# OpenAGBoardPart2.net
KiCad netlist of a schematic drawn in EAGLE
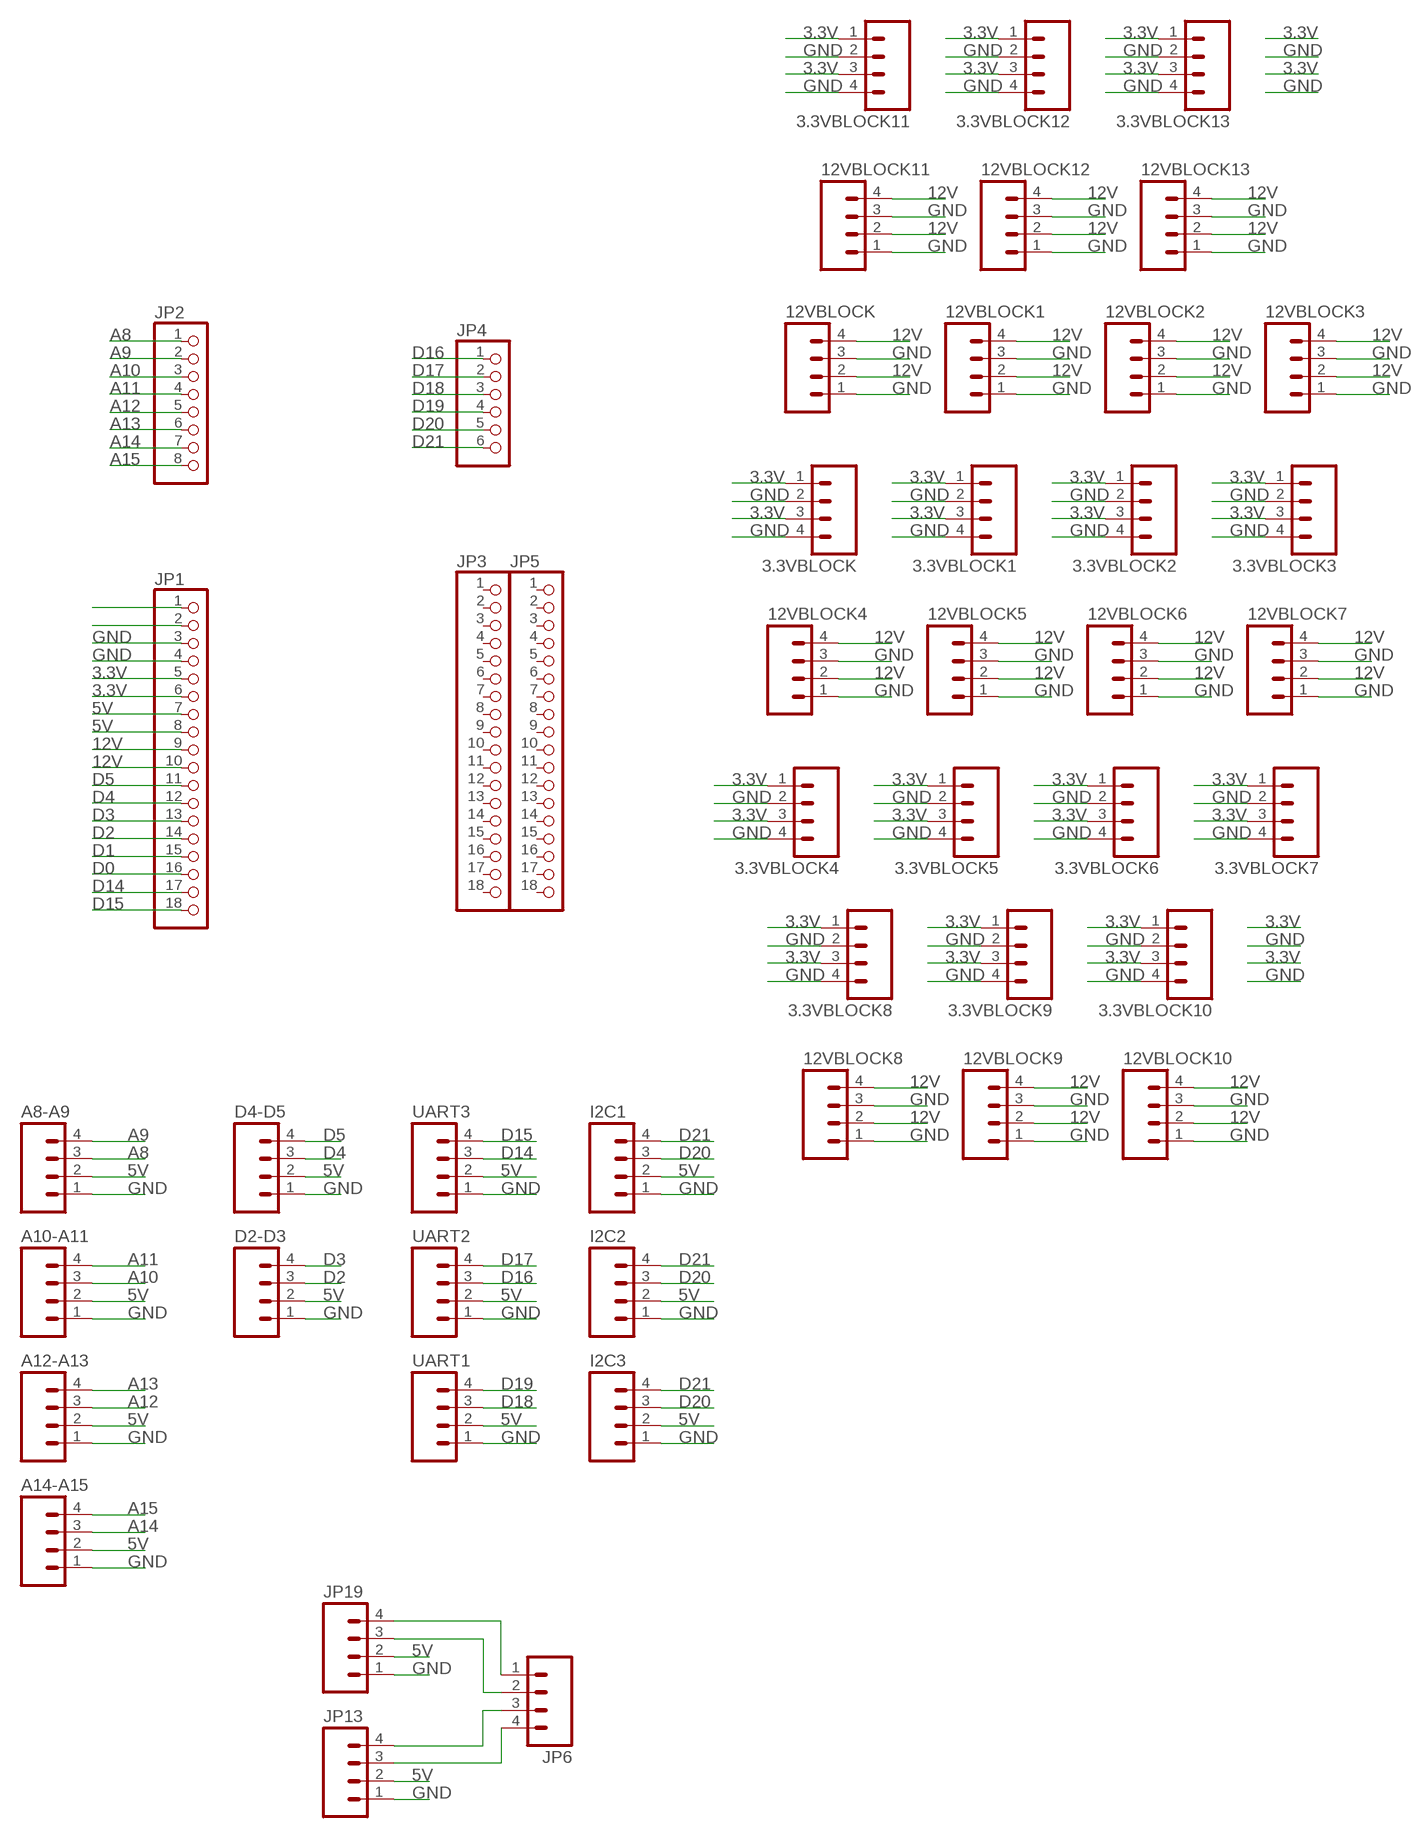
[diagram p0: schematic, sheet 1]

(export (version "E")
  (design (tool "Eeschema 10.0.6"))
  (components
    (comp (ref "3.3VBLOCK")
      (value "M04NO_SILK_ALL_ROUND")
      (footprint "eagle-import:1X04_NO_SILK_ALL_ROUND")
      (libsource (lib "eagle-import") (part "M04NO_SILK_ALL_ROUND"))
    )
    (comp (ref "3.3VBLOCK1")
      (value "M04NO_SILK_ALL_ROUND")
      (footprint "eagle-import:1X04_NO_SILK_ALL_ROUND")
      (libsource (lib "eagle-import") (part "M04NO_SILK_ALL_ROUND"))
    )
    (comp (ref "3.3VBLOCK2")
      (value "M04NO_SILK_ALL_ROUND")
      (footprint "eagle-import:1X04_NO_SILK_ALL_ROUND")
      (libsource (lib "eagle-import") (part "M04NO_SILK_ALL_ROUND"))
    )
    (comp (ref "3.3VBLOCK3")
      (value "M04NO_SILK_ALL_ROUND")
      (footprint "eagle-import:1X04_NO_SILK_ALL_ROUND")
      (libsource (lib "eagle-import") (part "M04NO_SILK_ALL_ROUND"))
    )
    (comp (ref "3.3VBLOCK4")
      (value "M04NO_SILK_ALL_ROUND")
      (footprint "eagle-import:1X04_NO_SILK_ALL_ROUND")
      (libsource (lib "eagle-import") (part "M04NO_SILK_ALL_ROUND"))
    )
    (comp (ref "3.3VBLOCK5")
      (value "M04NO_SILK_ALL_ROUND")
      (footprint "eagle-import:1X04_NO_SILK_ALL_ROUND")
      (libsource (lib "eagle-import") (part "M04NO_SILK_ALL_ROUND"))
    )
    (comp (ref "3.3VBLOCK6")
      (value "M04NO_SILK_ALL_ROUND")
      (footprint "eagle-import:1X04_NO_SILK_ALL_ROUND")
      (libsource (lib "eagle-import") (part "M04NO_SILK_ALL_ROUND"))
    )
    (comp (ref "3.3VBLOCK7")
      (value "M04NO_SILK_ALL_ROUND")
      (footprint "eagle-import:1X04_NO_SILK_ALL_ROUND")
      (libsource (lib "eagle-import") (part "M04NO_SILK_ALL_ROUND"))
    )
    (comp (ref "3.3VBLOCK8")
      (value "M04NO_SILK_ALL_ROUND")
      (footprint "eagle-import:1X04_NO_SILK_ALL_ROUND")
      (libsource (lib "eagle-import") (part "M04NO_SILK_ALL_ROUND"))
    )
    (comp (ref "3.3VBLOCK9")
      (value "M04NO_SILK_ALL_ROUND")
      (footprint "eagle-import:1X04_NO_SILK_ALL_ROUND")
      (libsource (lib "eagle-import") (part "M04NO_SILK_ALL_ROUND"))
    )
    (comp (ref "3.3VBLOCK10")
      (value "M04NO_SILK_ALL_ROUND")
      (footprint "eagle-import:1X04_NO_SILK_ALL_ROUND")
      (libsource (lib "eagle-import") (part "M04NO_SILK_ALL_ROUND"))
    )
    (comp (ref "3.3VBLOCK11")
      (value "M04NO_SILK_ALL_ROUND")
      (footprint "eagle-import:1X04_NO_SILK_ALL_ROUND")
      (libsource (lib "eagle-import") (part "M04NO_SILK_ALL_ROUND"))
    )
    (comp (ref "3.3VBLOCK12")
      (value "M04NO_SILK_ALL_ROUND")
      (footprint "eagle-import:1X04_NO_SILK_ALL_ROUND")
      (libsource (lib "eagle-import") (part "M04NO_SILK_ALL_ROUND"))
    )
    (comp (ref "3.3VBLOCK13")
      (value "M04NO_SILK_ALL_ROUND")
      (footprint "eagle-import:1X04_NO_SILK_ALL_ROUND")
      (libsource (lib "eagle-import") (part "M04NO_SILK_ALL_ROUND"))
    )
    (comp (ref "12VBLOCK")
      (value "M04NO_SILK_ALL_ROUND")
      (footprint "eagle-import:1X04_NO_SILK_ALL_ROUND")
      (libsource (lib "eagle-import") (part "M04NO_SILK_ALL_ROUND"))
    )
    (comp (ref "12VBLOCK1")
      (value "M04NO_SILK_ALL_ROUND")
      (footprint "eagle-import:1X04_NO_SILK_ALL_ROUND")
      (libsource (lib "eagle-import") (part "M04NO_SILK_ALL_ROUND"))
    )
    (comp (ref "12VBLOCK2")
      (value "M04NO_SILK_ALL_ROUND")
      (footprint "eagle-import:1X04_NO_SILK_ALL_ROUND")
      (libsource (lib "eagle-import") (part "M04NO_SILK_ALL_ROUND"))
    )
    (comp (ref "12VBLOCK3")
      (value "M04NO_SILK_ALL_ROUND")
      (footprint "eagle-import:1X04_NO_SILK_ALL_ROUND")
      (libsource (lib "eagle-import") (part "M04NO_SILK_ALL_ROUND"))
    )
    (comp (ref "12VBLOCK4")
      (value "M04NO_SILK_ALL_ROUND")
      (footprint "eagle-import:1X04_NO_SILK_ALL_ROUND")
      (libsource (lib "eagle-import") (part "M04NO_SILK_ALL_ROUND"))
    )
    (comp (ref "12VBLOCK5")
      (value "M04NO_SILK_ALL_ROUND")
      (footprint "eagle-import:1X04_NO_SILK_ALL_ROUND")
      (libsource (lib "eagle-import") (part "M04NO_SILK_ALL_ROUND"))
    )
    (comp (ref "12VBLOCK6")
      (value "M04NO_SILK_ALL_ROUND")
      (footprint "eagle-import:1X04_NO_SILK_ALL_ROUND")
      (libsource (lib "eagle-import") (part "M04NO_SILK_ALL_ROUND"))
    )
    (comp (ref "12VBLOCK7")
      (value "M04NO_SILK_ALL_ROUND")
      (footprint "eagle-import:1X04_NO_SILK_ALL_ROUND")
      (libsource (lib "eagle-import") (part "M04NO_SILK_ALL_ROUND"))
    )
    (comp (ref "12VBLOCK8")
      (value "M04NO_SILK_ALL_ROUND")
      (footprint "eagle-import:1X04_NO_SILK_ALL_ROUND")
      (libsource (lib "eagle-import") (part "M04NO_SILK_ALL_ROUND"))
    )
    (comp (ref "12VBLOCK9")
      (value "M04NO_SILK_ALL_ROUND")
      (footprint "eagle-import:1X04_NO_SILK_ALL_ROUND")
      (libsource (lib "eagle-import") (part "M04NO_SILK_ALL_ROUND"))
    )
    (comp (ref "12VBLOCK10")
      (value "M04NO_SILK_ALL_ROUND")
      (footprint "eagle-import:1X04_NO_SILK_ALL_ROUND")
      (libsource (lib "eagle-import") (part "M04NO_SILK_ALL_ROUND"))
    )
    (comp (ref "12VBLOCK11")
      (value "M04NO_SILK_ALL_ROUND")
      (footprint "eagle-import:1X04_NO_SILK_ALL_ROUND")
      (libsource (lib "eagle-import") (part "M04NO_SILK_ALL_ROUND"))
    )
    (comp (ref "12VBLOCK12")
      (value "M04NO_SILK_ALL_ROUND")
      (footprint "eagle-import:1X04_NO_SILK_ALL_ROUND")
      (libsource (lib "eagle-import") (part "M04NO_SILK_ALL_ROUND"))
    )
    (comp (ref "12VBLOCK13")
      (value "M04NO_SILK_ALL_ROUND")
      (footprint "eagle-import:1X04_NO_SILK_ALL_ROUND")
      (libsource (lib "eagle-import") (part "M04NO_SILK_ALL_ROUND"))
    )
    (comp (ref "A8-A9")
      (value "M04NO_SILK_ALL_ROUND")
      (footprint "eagle-import:1X04_NO_SILK_ALL_ROUND")
      (libsource (lib "eagle-import") (part "M04NO_SILK_ALL_ROUND"))
    )
    (comp (ref "A10-A11")
      (value "M04NO_SILK_ALL_ROUND")
      (footprint "eagle-import:1X04_NO_SILK_ALL_ROUND")
      (libsource (lib "eagle-import") (part "M04NO_SILK_ALL_ROUND"))
    )
    (comp (ref "A12-A13")
      (value "M04NO_SILK_ALL_ROUND")
      (footprint "eagle-import:1X04_NO_SILK_ALL_ROUND")
      (libsource (lib "eagle-import") (part "M04NO_SILK_ALL_ROUND"))
    )
    (comp (ref "A14-A15")
      (value "M04NO_SILK_ALL_ROUND")
      (footprint "eagle-import:1X04_NO_SILK_ALL_ROUND")
      (libsource (lib "eagle-import") (part "M04NO_SILK_ALL_ROUND"))
    )
    (comp (ref "D2-D3")
      (value "M04NO_SILK_ALL_ROUND")
      (footprint "eagle-import:1X04_NO_SILK_ALL_ROUND")
      (libsource (lib "eagle-import") (part "M04NO_SILK_ALL_ROUND"))
    )
    (comp (ref "D4-D5")
      (value "M04NO_SILK_ALL_ROUND")
      (footprint "eagle-import:1X04_NO_SILK_ALL_ROUND")
      (libsource (lib "eagle-import") (part "M04NO_SILK_ALL_ROUND"))
    )
    (comp (ref "I2C1")
      (value "M04NO_SILK_ALL_ROUND")
      (footprint "eagle-import:1X04_NO_SILK_ALL_ROUND")
      (libsource (lib "eagle-import") (part "M04NO_SILK_ALL_ROUND"))
    )
    (comp (ref "I2C2")
      (value "M04NO_SILK_ALL_ROUND")
      (footprint "eagle-import:1X04_NO_SILK_ALL_ROUND")
      (libsource (lib "eagle-import") (part "M04NO_SILK_ALL_ROUND"))
    )
    (comp (ref "I2C3")
      (value "M04NO_SILK_ALL_ROUND")
      (footprint "eagle-import:1X04_NO_SILK_ALL_ROUND")
      (libsource (lib "eagle-import") (part "M04NO_SILK_ALL_ROUND"))
    )
    (comp (ref "JP1")
      (value "PINHD-1X18-BIG")
      (footprint "eagle-import:1X18-BIG")
      (libsource (lib "eagle-import") (part "PINHD-1X18-BIG"))
    )
    (comp (ref "JP2")
      (value "PINHD-1X8BIG")
      (footprint "eagle-import:1X08-BIG")
      (libsource (lib "eagle-import") (part "PINHD-1X8BIG"))
    )
    (comp (ref "JP3")
      (value "PINHD-1X18-BIG")
      (footprint "eagle-import:1X18-BIG")
      (libsource (lib "eagle-import") (part "PINHD-1X18-BIG"))
    )
    (comp (ref "JP4")
      (value "PINHD-1X6B")
      (footprint "eagle-import:1X06-BIG")
      (libsource (lib "eagle-import") (part "PINHD-1X6B"))
    )
    (comp (ref "JP5")
      (value "PINHD-1X18-BIG")
      (footprint "eagle-import:1X18-BIG")
      (libsource (lib "eagle-import") (part "PINHD-1X18-BIG"))
    )
    (comp (ref "JP6")
      (value "M04PTH")
      (footprint "eagle-import:1X04")
      (libsource (lib "eagle-import") (part "M04PTH"))
    )
    (comp (ref "JP13")
      (value "M04NO_SILK_ALL_ROUND")
      (footprint "eagle-import:1X04_NO_SILK_ALL_ROUND")
      (libsource (lib "eagle-import") (part "M04NO_SILK_ALL_ROUND"))
    )
    (comp (ref "JP19")
      (value "M04NO_SILK_ALL_ROUND")
      (footprint "eagle-import:1X04_NO_SILK_ALL_ROUND")
      (libsource (lib "eagle-import") (part "M04NO_SILK_ALL_ROUND"))
    )
    (comp (ref "UART1")
      (value "M04NO_SILK_ALL_ROUND")
      (footprint "eagle-import:1X04_NO_SILK_ALL_ROUND")
      (libsource (lib "eagle-import") (part "M04NO_SILK_ALL_ROUND"))
    )
    (comp (ref "UART2")
      (value "M04NO_SILK_ALL_ROUND")
      (footprint "eagle-import:1X04_NO_SILK_ALL_ROUND")
      (libsource (lib "eagle-import") (part "M04NO_SILK_ALL_ROUND"))
    )
    (comp (ref "UART3")
      (value "M04NO_SILK_ALL_ROUND")
      (footprint "eagle-import:1X04_NO_SILK_ALL_ROUND")
      (libsource (lib "eagle-import") (part "M04NO_SILK_ALL_ROUND"))
    )
  )
  (nets
    (net (code "1") (name "/3.3V") (class "Default")
      (node (ref "3.3VBLOCK") (pin "1") (pinfunction "1_1") (pintype "passive"))
      (node (ref "3.3VBLOCK") (pin "3") (pinfunction "3_3") (pintype "passive"))
      (node (ref "3.3VBLOCK1") (pin "1") (pinfunction "1_1") (pintype "passive"))
      (node (ref "3.3VBLOCK1") (pin "3") (pinfunction "3_3") (pintype "passive"))
      (node (ref "3.3VBLOCK10") (pin "1") (pinfunction "1_1") (pintype "passive"))
      (node (ref "3.3VBLOCK10") (pin "3") (pinfunction "3_3") (pintype "passive"))
      (node (ref "3.3VBLOCK11") (pin "1") (pinfunction "1_1") (pintype "passive"))
      (node (ref "3.3VBLOCK11") (pin "3") (pinfunction "3_3") (pintype "passive"))
      (node (ref "3.3VBLOCK12") (pin "1") (pinfunction "1_1") (pintype "passive"))
      (node (ref "3.3VBLOCK12") (pin "3") (pinfunction "3_3") (pintype "passive"))
      (node (ref "3.3VBLOCK13") (pin "1") (pinfunction "1_1") (pintype "passive"))
      (node (ref "3.3VBLOCK13") (pin "3") (pinfunction "3_3") (pintype "passive"))
      (node (ref "3.3VBLOCK2") (pin "1") (pinfunction "1_1") (pintype "passive"))
      (node (ref "3.3VBLOCK2") (pin "3") (pinfunction "3_3") (pintype "passive"))
      (node (ref "3.3VBLOCK3") (pin "1") (pinfunction "1_1") (pintype "passive"))
      (node (ref "3.3VBLOCK3") (pin "3") (pinfunction "3_3") (pintype "passive"))
      (node (ref "3.3VBLOCK4") (pin "1") (pinfunction "1_1") (pintype "passive"))
      (node (ref "3.3VBLOCK4") (pin "3") (pinfunction "3_3") (pintype "passive"))
      (node (ref "3.3VBLOCK5") (pin "1") (pinfunction "1_1") (pintype "passive"))
      (node (ref "3.3VBLOCK5") (pin "3") (pinfunction "3_3") (pintype "passive"))
      (node (ref "3.3VBLOCK6") (pin "1") (pinfunction "1_1") (pintype "passive"))
      (node (ref "3.3VBLOCK6") (pin "3") (pinfunction "3_3") (pintype "passive"))
      (node (ref "3.3VBLOCK7") (pin "1") (pinfunction "1_1") (pintype "passive"))
      (node (ref "3.3VBLOCK7") (pin "3") (pinfunction "3_3") (pintype "passive"))
      (node (ref "3.3VBLOCK8") (pin "1") (pinfunction "1_1") (pintype "passive"))
      (node (ref "3.3VBLOCK8") (pin "3") (pinfunction "3_3") (pintype "passive"))
      (node (ref "3.3VBLOCK9") (pin "1") (pinfunction "1_1") (pintype "passive"))
      (node (ref "3.3VBLOCK9") (pin "3") (pinfunction "3_3") (pintype "passive"))
      (node (ref "JP1") (pin "5") (pinfunction "5_5") (pintype "passive"))
      (node (ref "JP1") (pin "6") (pinfunction "6_6") (pintype "passive"))
    )
    (net (code "2") (name "/5V") (class "Default")
      (node (ref "A10-A11") (pin "2") (pinfunction "2_2") (pintype "passive"))
      (node (ref "A12-A13") (pin "2") (pinfunction "2_2") (pintype "passive"))
      (node (ref "A14-A15") (pin "2") (pinfunction "2_2") (pintype "passive"))
      (node (ref "A8-A9") (pin "2") (pinfunction "2_2") (pintype "passive"))
      (node (ref "D2-D3") (pin "2") (pinfunction "2_2") (pintype "passive"))
      (node (ref "D4-D5") (pin "2") (pinfunction "2_2") (pintype "passive"))
      (node (ref "I2C1") (pin "2") (pinfunction "2_2") (pintype "passive"))
      (node (ref "I2C2") (pin "2") (pinfunction "2_2") (pintype "passive"))
      (node (ref "I2C3") (pin "2") (pinfunction "2_2") (pintype "passive"))
      (node (ref "JP1") (pin "7") (pinfunction "7_7") (pintype "passive"))
      (node (ref "JP1") (pin "8") (pinfunction "8_8") (pintype "passive"))
      (node (ref "JP13") (pin "2") (pinfunction "2_2") (pintype "passive"))
      (node (ref "JP19") (pin "2") (pinfunction "2_2") (pintype "passive"))
      (node (ref "UART1") (pin "2") (pinfunction "2_2") (pintype "passive"))
      (node (ref "UART2") (pin "2") (pinfunction "2_2") (pintype "passive"))
      (node (ref "UART3") (pin "2") (pinfunction "2_2") (pintype "passive"))
    )
    (net (code "3") (name "/12V") (class "Default")
      (node (ref "12VBLOCK") (pin "2") (pinfunction "2_2") (pintype "passive"))
      (node (ref "12VBLOCK") (pin "4") (pinfunction "4_4") (pintype "passive"))
      (node (ref "12VBLOCK1") (pin "2") (pinfunction "2_2") (pintype "passive"))
      (node (ref "12VBLOCK1") (pin "4") (pinfunction "4_4") (pintype "passive"))
      (node (ref "12VBLOCK10") (pin "2") (pinfunction "2_2") (pintype "passive"))
      (node (ref "12VBLOCK10") (pin "4") (pinfunction "4_4") (pintype "passive"))
      (node (ref "12VBLOCK11") (pin "2") (pinfunction "2_2") (pintype "passive"))
      (node (ref "12VBLOCK11") (pin "4") (pinfunction "4_4") (pintype "passive"))
      (node (ref "12VBLOCK12") (pin "2") (pinfunction "2_2") (pintype "passive"))
      (node (ref "12VBLOCK12") (pin "4") (pinfunction "4_4") (pintype "passive"))
      (node (ref "12VBLOCK13") (pin "2") (pinfunction "2_2") (pintype "passive"))
      (node (ref "12VBLOCK13") (pin "4") (pinfunction "4_4") (pintype "passive"))
      (node (ref "12VBLOCK2") (pin "2") (pinfunction "2_2") (pintype "passive"))
      (node (ref "12VBLOCK2") (pin "4") (pinfunction "4_4") (pintype "passive"))
      (node (ref "12VBLOCK3") (pin "2") (pinfunction "2_2") (pintype "passive"))
      (node (ref "12VBLOCK3") (pin "4") (pinfunction "4_4") (pintype "passive"))
      (node (ref "12VBLOCK4") (pin "2") (pinfunction "2_2") (pintype "passive"))
      (node (ref "12VBLOCK4") (pin "4") (pinfunction "4_4") (pintype "passive"))
      (node (ref "12VBLOCK5") (pin "2") (pinfunction "2_2") (pintype "passive"))
      (node (ref "12VBLOCK5") (pin "4") (pinfunction "4_4") (pintype "passive"))
      (node (ref "12VBLOCK6") (pin "2") (pinfunction "2_2") (pintype "passive"))
      (node (ref "12VBLOCK6") (pin "4") (pinfunction "4_4") (pintype "passive"))
      (node (ref "12VBLOCK7") (pin "2") (pinfunction "2_2") (pintype "passive"))
      (node (ref "12VBLOCK7") (pin "4") (pinfunction "4_4") (pintype "passive"))
      (node (ref "12VBLOCK8") (pin "2") (pinfunction "2_2") (pintype "passive"))
      (node (ref "12VBLOCK8") (pin "4") (pinfunction "4_4") (pintype "passive"))
      (node (ref "12VBLOCK9") (pin "2") (pinfunction "2_2") (pintype "passive"))
      (node (ref "12VBLOCK9") (pin "4") (pinfunction "4_4") (pintype "passive"))
      (node (ref "JP1") (pin "10") (pinfunction "10_10") (pintype "passive"))
      (node (ref "JP1") (pin "9") (pinfunction "9_9") (pintype "passive"))
    )
    (net (code "4") (name "/A8") (class "Default")
      (node (ref "A8-A9") (pin "3") (pinfunction "3_3") (pintype "passive"))
      (node (ref "JP2") (pin "1") (pinfunction "1_1") (pintype "passive"))
    )
    (net (code "5") (name "/A9") (class "Default")
      (node (ref "A8-A9") (pin "4") (pinfunction "4_4") (pintype "passive"))
      (node (ref "JP2") (pin "2") (pinfunction "2_2") (pintype "passive"))
    )
    (net (code "6") (name "/A10") (class "Default")
      (node (ref "A10-A11") (pin "3") (pinfunction "3_3") (pintype "passive"))
      (node (ref "JP2") (pin "3") (pinfunction "3_3") (pintype "passive"))
    )
    (net (code "7") (name "/A11") (class "Default")
      (node (ref "A10-A11") (pin "4") (pinfunction "4_4") (pintype "passive"))
      (node (ref "JP2") (pin "4") (pinfunction "4_4") (pintype "passive"))
    )
    (net (code "8") (name "/A12") (class "Default")
      (node (ref "A12-A13") (pin "3") (pinfunction "3_3") (pintype "passive"))
      (node (ref "JP2") (pin "5") (pinfunction "5_5") (pintype "passive"))
    )
    (net (code "9") (name "/A13") (class "Default")
      (node (ref "A12-A13") (pin "4") (pinfunction "4_4") (pintype "passive"))
      (node (ref "JP2") (pin "6") (pinfunction "6_6") (pintype "passive"))
    )
    (net (code "10") (name "/A14") (class "Default")
      (node (ref "A14-A15") (pin "3") (pinfunction "3_3") (pintype "passive"))
      (node (ref "JP2") (pin "7") (pinfunction "7_7") (pintype "passive"))
    )
    (net (code "11") (name "/A15") (class "Default")
      (node (ref "A14-A15") (pin "4") (pinfunction "4_4") (pintype "passive"))
      (node (ref "JP2") (pin "8") (pinfunction "8_8") (pintype "passive"))
    )
    (net (code "12") (name "/D0") (class "Default")
      (node (ref "JP1") (pin "16") (pinfunction "16_16") (pintype "passive"))
    )
    (net (code "13") (name "/D1") (class "Default")
      (node (ref "JP1") (pin "15") (pinfunction "15_15") (pintype "passive"))
    )
    (net (code "14") (name "/D2") (class "Default")
      (node (ref "D2-D3") (pin "3") (pinfunction "3_3") (pintype "passive"))
      (node (ref "JP1") (pin "14") (pinfunction "14_14") (pintype "passive"))
    )
    (net (code "15") (name "/D3") (class "Default")
      (node (ref "D2-D3") (pin "4") (pinfunction "4_4") (pintype "passive"))
      (node (ref "JP1") (pin "13") (pinfunction "13_13") (pintype "passive"))
    )
    (net (code "16") (name "/D4") (class "Default")
      (node (ref "D4-D5") (pin "3") (pinfunction "3_3") (pintype "passive"))
      (node (ref "JP1") (pin "12") (pinfunction "12_12") (pintype "passive"))
    )
    (net (code "17") (name "/D5") (class "Default")
      (node (ref "D4-D5") (pin "4") (pinfunction "4_4") (pintype "passive"))
      (node (ref "JP1") (pin "11") (pinfunction "11_11") (pintype "passive"))
    )
    (net (code "18") (name "/D14") (class "Default")
      (node (ref "JP1") (pin "17") (pinfunction "17_17") (pintype "passive"))
      (node (ref "UART3") (pin "3") (pinfunction "3_3") (pintype "passive"))
    )
    (net (code "19") (name "/D15") (class "Default")
      (node (ref "JP1") (pin "18") (pinfunction "18_18") (pintype "passive"))
      (node (ref "UART3") (pin "4") (pinfunction "4_4") (pintype "passive"))
    )
    (net (code "20") (name "/D16") (class "Default")
      (node (ref "JP4") (pin "1") (pinfunction "1_1") (pintype "passive"))
      (node (ref "UART2") (pin "3") (pinfunction "3_3") (pintype "passive"))
    )
    (net (code "21") (name "/D17") (class "Default")
      (node (ref "JP4") (pin "2") (pinfunction "2_2") (pintype "passive"))
      (node (ref "UART2") (pin "4") (pinfunction "4_4") (pintype "passive"))
    )
    (net (code "22") (name "/D18") (class "Default")
      (node (ref "JP4") (pin "3") (pinfunction "3_3") (pintype "passive"))
      (node (ref "UART1") (pin "3") (pinfunction "3_3") (pintype "passive"))
    )
    (net (code "23") (name "/D19") (class "Default")
      (node (ref "JP4") (pin "4") (pinfunction "4_4") (pintype "passive"))
      (node (ref "UART1") (pin "4") (pinfunction "4_4") (pintype "passive"))
    )
    (net (code "24") (name "/D20") (class "Default")
      (node (ref "I2C1") (pin "3") (pinfunction "3_3") (pintype "passive"))
      (node (ref "I2C2") (pin "3") (pinfunction "3_3") (pintype "passive"))
      (node (ref "I2C3") (pin "3") (pinfunction "3_3") (pintype "passive"))
      (node (ref "JP4") (pin "5") (pinfunction "5_5") (pintype "passive"))
    )
    (net (code "25") (name "/D21") (class "Default")
      (node (ref "I2C1") (pin "4") (pinfunction "4_4") (pintype "passive"))
      (node (ref "I2C2") (pin "4") (pinfunction "4_4") (pintype "passive"))
      (node (ref "I2C3") (pin "4") (pinfunction "4_4") (pintype "passive"))
      (node (ref "JP4") (pin "6") (pinfunction "6_6") (pintype "passive"))
    )
    (net (code "26") (name "/GND") (class "Default")
      (node (ref "12VBLOCK") (pin "1") (pinfunction "1_1") (pintype "passive"))
      (node (ref "12VBLOCK") (pin "3") (pinfunction "3_3") (pintype "passive"))
      (node (ref "12VBLOCK1") (pin "1") (pinfunction "1_1") (pintype "passive"))
      (node (ref "12VBLOCK1") (pin "3") (pinfunction "3_3") (pintype "passive"))
      (node (ref "12VBLOCK10") (pin "1") (pinfunction "1_1") (pintype "passive"))
      (node (ref "12VBLOCK10") (pin "3") (pinfunction "3_3") (pintype "passive"))
      (node (ref "12VBLOCK11") (pin "1") (pinfunction "1_1") (pintype "passive"))
      (node (ref "12VBLOCK11") (pin "3") (pinfunction "3_3") (pintype "passive"))
      (node (ref "12VBLOCK12") (pin "1") (pinfunction "1_1") (pintype "passive"))
      (node (ref "12VBLOCK12") (pin "3") (pinfunction "3_3") (pintype "passive"))
      (node (ref "12VBLOCK13") (pin "1") (pinfunction "1_1") (pintype "passive"))
      (node (ref "12VBLOCK13") (pin "3") (pinfunction "3_3") (pintype "passive"))
      (node (ref "12VBLOCK2") (pin "1") (pinfunction "1_1") (pintype "passive"))
      (node (ref "12VBLOCK2") (pin "3") (pinfunction "3_3") (pintype "passive"))
      (node (ref "12VBLOCK3") (pin "1") (pinfunction "1_1") (pintype "passive"))
      (node (ref "12VBLOCK3") (pin "3") (pinfunction "3_3") (pintype "passive"))
      (node (ref "12VBLOCK4") (pin "1") (pinfunction "1_1") (pintype "passive"))
      (node (ref "12VBLOCK4") (pin "3") (pinfunction "3_3") (pintype "passive"))
      (node (ref "12VBLOCK5") (pin "1") (pinfunction "1_1") (pintype "passive"))
      (node (ref "12VBLOCK5") (pin "3") (pinfunction "3_3") (pintype "passive"))
      (node (ref "12VBLOCK6") (pin "1") (pinfunction "1_1") (pintype "passive"))
      (node (ref "12VBLOCK6") (pin "3") (pinfunction "3_3") (pintype "passive"))
      (node (ref "12VBLOCK7") (pin "1") (pinfunction "1_1") (pintype "passive"))
      (node (ref "12VBLOCK7") (pin "3") (pinfunction "3_3") (pintype "passive"))
      (node (ref "12VBLOCK8") (pin "1") (pinfunction "1_1") (pintype "passive"))
      (node (ref "12VBLOCK8") (pin "3") (pinfunction "3_3") (pintype "passive"))
      (node (ref "12VBLOCK9") (pin "1") (pinfunction "1_1") (pintype "passive"))
      (node (ref "12VBLOCK9") (pin "3") (pinfunction "3_3") (pintype "passive"))
      (node (ref "3.3VBLOCK") (pin "2") (pinfunction "2_2") (pintype "passive"))
      (node (ref "3.3VBLOCK") (pin "4") (pinfunction "4_4") (pintype "passive"))
      (node (ref "3.3VBLOCK1") (pin "2") (pinfunction "2_2") (pintype "passive"))
      (node (ref "3.3VBLOCK1") (pin "4") (pinfunction "4_4") (pintype "passive"))
      (node (ref "3.3VBLOCK10") (pin "2") (pinfunction "2_2") (pintype "passive"))
      (node (ref "3.3VBLOCK10") (pin "4") (pinfunction "4_4") (pintype "passive"))
      (node (ref "3.3VBLOCK11") (pin "2") (pinfunction "2_2") (pintype "passive"))
      (node (ref "3.3VBLOCK11") (pin "4") (pinfunction "4_4") (pintype "passive"))
      (node (ref "3.3VBLOCK12") (pin "2") (pinfunction "2_2") (pintype "passive"))
      (node (ref "3.3VBLOCK12") (pin "4") (pinfunction "4_4") (pintype "passive"))
      (node (ref "3.3VBLOCK13") (pin "2") (pinfunction "2_2") (pintype "passive"))
      (node (ref "3.3VBLOCK13") (pin "4") (pinfunction "4_4") (pintype "passive"))
      (node (ref "3.3VBLOCK2") (pin "2") (pinfunction "2_2") (pintype "passive"))
      (node (ref "3.3VBLOCK2") (pin "4") (pinfunction "4_4") (pintype "passive"))
      (node (ref "3.3VBLOCK3") (pin "2") (pinfunction "2_2") (pintype "passive"))
      (node (ref "3.3VBLOCK3") (pin "4") (pinfunction "4_4") (pintype "passive"))
      (node (ref "3.3VBLOCK4") (pin "2") (pinfunction "2_2") (pintype "passive"))
      (node (ref "3.3VBLOCK4") (pin "4") (pinfunction "4_4") (pintype "passive"))
      (node (ref "3.3VBLOCK5") (pin "2") (pinfunction "2_2") (pintype "passive"))
      (node (ref "3.3VBLOCK5") (pin "4") (pinfunction "4_4") (pintype "passive"))
      (node (ref "3.3VBLOCK6") (pin "2") (pinfunction "2_2") (pintype "passive"))
      (node (ref "3.3VBLOCK6") (pin "4") (pinfunction "4_4") (pintype "passive"))
      (node (ref "3.3VBLOCK7") (pin "2") (pinfunction "2_2") (pintype "passive"))
      (node (ref "3.3VBLOCK7") (pin "4") (pinfunction "4_4") (pintype "passive"))
      (node (ref "3.3VBLOCK8") (pin "2") (pinfunction "2_2") (pintype "passive"))
      (node (ref "3.3VBLOCK8") (pin "4") (pinfunction "4_4") (pintype "passive"))
      (node (ref "3.3VBLOCK9") (pin "2") (pinfunction "2_2") (pintype "passive"))
      (node (ref "3.3VBLOCK9") (pin "4") (pinfunction "4_4") (pintype "passive"))
      (node (ref "A10-A11") (pin "1") (pinfunction "1_1") (pintype "passive"))
      (node (ref "A12-A13") (pin "1") (pinfunction "1_1") (pintype "passive"))
      (node (ref "A14-A15") (pin "1") (pinfunction "1_1") (pintype "passive"))
      (node (ref "A8-A9") (pin "1") (pinfunction "1_1") (pintype "passive"))
      (node (ref "D2-D3") (pin "1") (pinfunction "1_1") (pintype "passive"))
      (node (ref "D4-D5") (pin "1") (pinfunction "1_1") (pintype "passive"))
      (node (ref "I2C1") (pin "1") (pinfunction "1_1") (pintype "passive"))
      (node (ref "I2C2") (pin "1") (pinfunction "1_1") (pintype "passive"))
      (node (ref "I2C3") (pin "1") (pinfunction "1_1") (pintype "passive"))
      (node (ref "JP1") (pin "3") (pinfunction "3_3") (pintype "passive"))
      (node (ref "JP1") (pin "4") (pinfunction "4_4") (pintype "passive"))
      (node (ref "JP13") (pin "1") (pinfunction "1_1") (pintype "passive"))
      (node (ref "JP19") (pin "1") (pinfunction "1_1") (pintype "passive"))
      (node (ref "UART1") (pin "1") (pinfunction "1_1") (pintype "passive"))
      (node (ref "UART2") (pin "1") (pinfunction "1_1") (pintype "passive"))
      (node (ref "UART3") (pin "1") (pinfunction "1_1") (pintype "passive"))
    )
    (net (code "27") (name "Net-(JP13-Pad3)") (class "Default")
      (node (ref "JP13") (pin "3") (pinfunction "3_3") (pintype "passive"))
      (node (ref "JP6") (pin "4") (pinfunction "4_4") (pintype "passive"))
    )
    (net (code "28") (name "Net-(JP13-Pad4)") (class "Default")
      (node (ref "JP13") (pin "4") (pinfunction "4_4") (pintype "passive"))
      (node (ref "JP6") (pin "3") (pinfunction "3_3") (pintype "passive"))
    )
    (net (code "29") (name "Net-(JP19-Pad3)") (class "Default")
      (node (ref "JP19") (pin "3") (pinfunction "3_3") (pintype "passive"))
      (node (ref "JP6") (pin "2") (pinfunction "2_2") (pintype "passive"))
    )
    (net (code "30") (name "Net-(JP19-Pad4)") (class "Default")
      (node (ref "JP19") (pin "4") (pinfunction "4_4") (pintype "passive"))
      (node (ref "JP6") (pin "1") (pinfunction "1_1") (pintype "passive"))
    )
    (net (code "31") (name "unconnected-(JP1-Pad1)") (class "Default")
      (node (ref "JP1") (pin "1") (pinfunction "1_1") (pintype "passive"))
    )
    (net (code "32") (name "unconnected-(JP1-Pad2)") (class "Default")
      (node (ref "JP1") (pin "2") (pinfunction "2_2") (pintype "passive"))
    )
    (net (code "33") (name "unconnected-(JP3-Pad1)") (class "Default")
      (node (ref "JP3") (pin "1") (pinfunction "1_1") (pintype "passive"))
    )
    (net (code "34") (name "unconnected-(JP3-Pad2)") (class "Default")
      (node (ref "JP3") (pin "2") (pinfunction "2_2") (pintype "passive"))
    )
    (net (code "35") (name "unconnected-(JP3-Pad3)") (class "Default")
      (node (ref "JP3") (pin "3") (pinfunction "3_3") (pintype "passive"))
    )
    (net (code "36") (name "unconnected-(JP3-Pad4)") (class "Default")
      (node (ref "JP3") (pin "4") (pinfunction "4_4") (pintype "passive"))
    )
    (net (code "37") (name "unconnected-(JP3-Pad5)") (class "Default")
      (node (ref "JP3") (pin "5") (pinfunction "5_5") (pintype "passive"))
    )
    (net (code "38") (name "unconnected-(JP3-Pad6)") (class "Default")
      (node (ref "JP3") (pin "6") (pinfunction "6_6") (pintype "passive"))
    )
    (net (code "39") (name "unconnected-(JP3-Pad7)") (class "Default")
      (node (ref "JP3") (pin "7") (pinfunction "7_7") (pintype "passive"))
    )
    (net (code "40") (name "unconnected-(JP3-Pad8)") (class "Default")
      (node (ref "JP3") (pin "8") (pinfunction "8_8") (pintype "passive"))
    )
    (net (code "41") (name "unconnected-(JP3-Pad9)") (class "Default")
      (node (ref "JP3") (pin "9") (pinfunction "9_9") (pintype "passive"))
    )
    (net (code "42") (name "unconnected-(JP3-Pad10)") (class "Default")
      (node (ref "JP3") (pin "10") (pinfunction "10_10") (pintype "passive"))
    )
    (net (code "43") (name "unconnected-(JP3-Pad11)") (class "Default")
      (node (ref "JP3") (pin "11") (pinfunction "11_11") (pintype "passive"))
    )
    (net (code "44") (name "unconnected-(JP3-Pad12)") (class "Default")
      (node (ref "JP3") (pin "12") (pinfunction "12_12") (pintype "passive"))
    )
    (net (code "45") (name "unconnected-(JP3-Pad13)") (class "Default")
      (node (ref "JP3") (pin "13") (pinfunction "13_13") (pintype "passive"))
    )
    (net (code "46") (name "unconnected-(JP3-Pad14)") (class "Default")
      (node (ref "JP3") (pin "14") (pinfunction "14_14") (pintype "passive"))
    )
    (net (code "47") (name "unconnected-(JP3-Pad15)") (class "Default")
      (node (ref "JP3") (pin "15") (pinfunction "15_15") (pintype "passive"))
    )
    (net (code "48") (name "unconnected-(JP3-Pad16)") (class "Default")
      (node (ref "JP3") (pin "16") (pinfunction "16_16") (pintype "passive"))
    )
    (net (code "49") (name "unconnected-(JP3-Pad17)") (class "Default")
      (node (ref "JP3") (pin "17") (pinfunction "17_17") (pintype "passive"))
    )
    (net (code "50") (name "unconnected-(JP3-Pad18)") (class "Default")
      (node (ref "JP3") (pin "18") (pinfunction "18_18") (pintype "passive"))
    )
    (net (code "51") (name "unconnected-(JP5-Pad1)") (class "Default")
      (node (ref "JP5") (pin "1") (pinfunction "1_1") (pintype "passive"))
    )
    (net (code "52") (name "unconnected-(JP5-Pad2)") (class "Default")
      (node (ref "JP5") (pin "2") (pinfunction "2_2") (pintype "passive"))
    )
    (net (code "53") (name "unconnected-(JP5-Pad3)") (class "Default")
      (node (ref "JP5") (pin "3") (pinfunction "3_3") (pintype "passive"))
    )
    (net (code "54") (name "unconnected-(JP5-Pad4)") (class "Default")
      (node (ref "JP5") (pin "4") (pinfunction "4_4") (pintype "passive"))
    )
    (net (code "55") (name "unconnected-(JP5-Pad5)") (class "Default")
      (node (ref "JP5") (pin "5") (pinfunction "5_5") (pintype "passive"))
    )
    (net (code "56") (name "unconnected-(JP5-Pad6)") (class "Default")
      (node (ref "JP5") (pin "6") (pinfunction "6_6") (pintype "passive"))
    )
    (net (code "57") (name "unconnected-(JP5-Pad7)") (class "Default")
      (node (ref "JP5") (pin "7") (pinfunction "7_7") (pintype "passive"))
    )
    (net (code "58") (name "unconnected-(JP5-Pad8)") (class "Default")
      (node (ref "JP5") (pin "8") (pinfunction "8_8") (pintype "passive"))
    )
    (net (code "59") (name "unconnected-(JP5-Pad9)") (class "Default")
      (node (ref "JP5") (pin "9") (pinfunction "9_9") (pintype "passive"))
    )
    (net (code "60") (name "unconnected-(JP5-Pad10)") (class "Default")
      (node (ref "JP5") (pin "10") (pinfunction "10_10") (pintype "passive"))
    )
    (net (code "61") (name "unconnected-(JP5-Pad11)") (class "Default")
      (node (ref "JP5") (pin "11") (pinfunction "11_11") (pintype "passive"))
    )
    (net (code "62") (name "unconnected-(JP5-Pad12)") (class "Default")
      (node (ref "JP5") (pin "12") (pinfunction "12_12") (pintype "passive"))
    )
    (net (code "63") (name "unconnected-(JP5-Pad13)") (class "Default")
      (node (ref "JP5") (pin "13") (pinfunction "13_13") (pintype "passive"))
    )
    (net (code "64") (name "unconnected-(JP5-Pad14)") (class "Default")
      (node (ref "JP5") (pin "14") (pinfunction "14_14") (pintype "passive"))
    )
    (net (code "65") (name "unconnected-(JP5-Pad15)") (class "Default")
      (node (ref "JP5") (pin "15") (pinfunction "15_15") (pintype "passive"))
    )
    (net (code "66") (name "unconnected-(JP5-Pad16)") (class "Default")
      (node (ref "JP5") (pin "16") (pinfunction "16_16") (pintype "passive"))
    )
    (net (code "67") (name "unconnected-(JP5-Pad17)") (class "Default")
      (node (ref "JP5") (pin "17") (pinfunction "17_17") (pintype "passive"))
    )
    (net (code "68") (name "unconnected-(JP5-Pad18)") (class "Default")
      (node (ref "JP5") (pin "18") (pinfunction "18_18") (pintype "passive"))
    )
  )
)
